# esp32.net
KiCad netlist of a schematic drawn in EAGLE
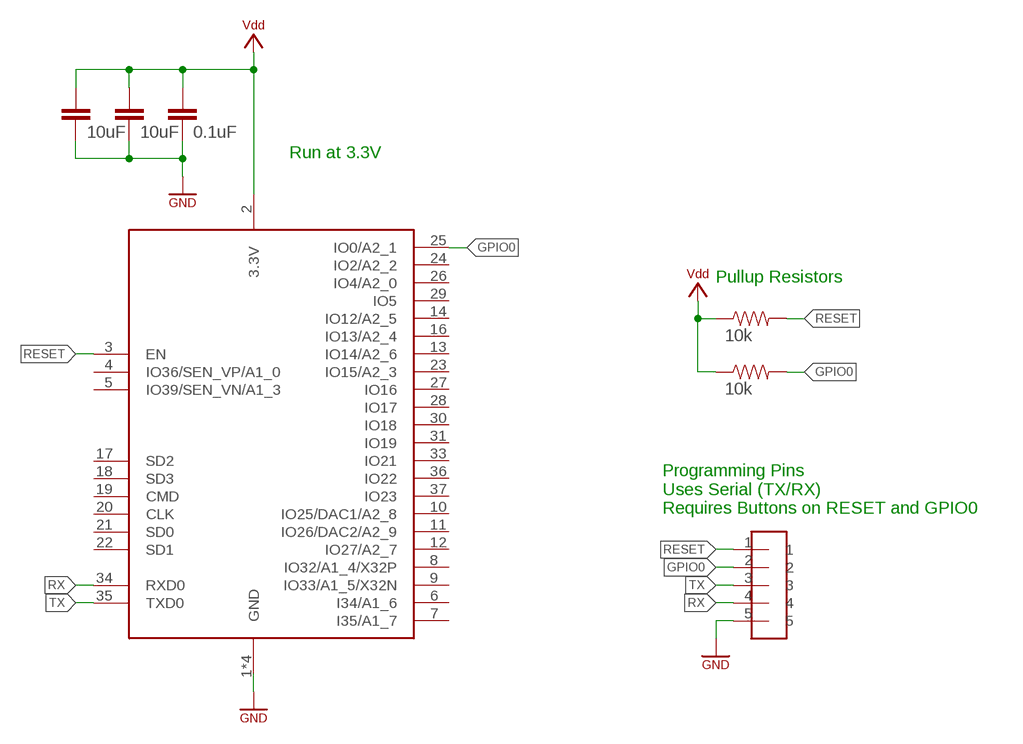
[diagram p0: schematic, sheet 1]

(export (version "E")
  (design (tool "Eeschema 10.0.6"))
  (components
    (comp (ref "C1")
      (value "0.1uF")
      (footprint "eagle-import:0805")
      (libsource (lib "eagle-import") (part "COMPONENT_CAP-0805"))
    )
    (comp (ref "C2")
      (value "10uF")
      (footprint "eagle-import:0805")
      (libsource (lib "eagle-import") (part "COMPONENT_CAP-0805"))
    )
    (comp (ref "C3")
      (value "10uF")
      (footprint "eagle-import:0805")
      (libsource (lib "eagle-import") (part "COMPONENT_CAP-0805"))
    )
    (comp (ref "R1")
      (value "10k")
      (footprint "eagle-import:0805")
      (libsource (lib "eagle-import") (part "COMPONENT_RESISTOR-0805"))
    )
    (comp (ref "R2")
      (value "10k")
      (footprint "eagle-import:0805")
      (libsource (lib "eagle-import") (part "COMPONENT_RESISTOR-0805"))
    )
    (comp (ref "U$1")
      (value "HEADER-5-TESTPOINT")
      (footprint "eagle-import:TESTPOINT-5")
      (libsource (lib "eagle-import") (part "HEADER-5-TESTPOINT"))
    )
    (comp (ref "X1")
      (value "MICRO_ESP32")
      (footprint "eagle-import:WROOM32")
      (libsource (lib "eagle-import") (part "MICRO_ESP32"))
    )
  )
  (nets
    (net (code "1") (name "GPIO0") (class "Default")
      (node (ref "R2") (pin "2") (pinfunction "2_2") (pintype "passive"))
      (node (ref "U$1") (pin "2") (pinfunction "2_2") (pintype "bidirectional"))
      (node (ref "X1") (pin "25") (pinfunction "IO0/A2_1_25") (pintype "bidirectional"))
    )
    (net (code "2") (name "RESET") (class "Default")
      (node (ref "R1") (pin "2") (pinfunction "2_2") (pintype "passive"))
      (node (ref "U$1") (pin "1") (pinfunction "1_1") (pintype "bidirectional"))
      (node (ref "X1") (pin "3") (pinfunction "EN_3") (pintype "input"))
    )
    (net (code "3") (name "RX") (class "Default")
      (node (ref "U$1") (pin "4") (pinfunction "4_4") (pintype "bidirectional"))
      (node (ref "X1") (pin "34") (pinfunction "RXD0_34") (pintype "input"))
    )
    (net (code "4") (name "SYMBOL_GND") (class "Default")
      (node (ref "C1") (pin "2") (pinfunction "2_2") (pintype "passive"))
      (node (ref "C2") (pin "2") (pinfunction "2_2") (pintype "passive"))
      (node (ref "C3") (pin "2") (pinfunction "2_2") (pintype "passive"))
      (node (ref "U$1") (pin "5") (pinfunction "5_5") (pintype "bidirectional"))
      (node (ref "X1") (pin "1") (pinfunction "GND_1") (pintype "passive"))
      (node (ref "X1") (pin "15") (pinfunction "GND_15") (pintype "passive"))
      (node (ref "X1") (pin "38") (pinfunction "GND_38") (pintype "passive"))
      (node (ref "X1") (pin "P$1") (pinfunction "GND_P$1") (pintype "passive"))
    )
    (net (code "5") (name "SYMBOL_VDD") (class "Default")
      (node (ref "C1") (pin "1") (pinfunction "1_1") (pintype "passive"))
      (node (ref "C2") (pin "1") (pinfunction "1_1") (pintype "passive"))
      (node (ref "C3") (pin "1") (pinfunction "1_1") (pintype "passive"))
      (node (ref "R1") (pin "1") (pinfunction "1_1") (pintype "passive"))
      (node (ref "R2") (pin "1") (pinfunction "1_1") (pintype "passive"))
      (node (ref "X1") (pin "2") (pinfunction "3.3V_2") (pintype "passive"))
    )
    (net (code "6") (name "TX") (class "Default")
      (node (ref "U$1") (pin "3") (pinfunction "3_3") (pintype "bidirectional"))
      (node (ref "X1") (pin "35") (pinfunction "TXD0_35") (pintype "output"))
    )
    (net (code "7") (name "unconnected-(X1-CLK-Pad20)") (class "Default")
      (node (ref "X1") (pin "20") (pinfunction "CLK_20") (pintype "bidirectional"))
    )
    (net (code "8") (name "unconnected-(X1-CMD-Pad19)") (class "Default")
      (node (ref "X1") (pin "19") (pinfunction "CMD_19") (pintype "bidirectional"))
    )
    (net (code "9") (name "unconnected-(X1-I34{slash}A1_6-Pad6)") (class "Default")
      (node (ref "X1") (pin "6") (pinfunction "I34/A1_6_6") (pintype "bidirectional"))
    )
    (net (code "10") (name "unconnected-(X1-I35{slash}A1_7-Pad7)") (class "Default")
      (node (ref "X1") (pin "7") (pinfunction "I35/A1_7_7") (pintype "bidirectional"))
    )
    (net (code "11") (name "unconnected-(X1-IO2{slash}A2_2-Pad24)") (class "Default")
      (node (ref "X1") (pin "24") (pinfunction "IO2/A2_2_24") (pintype "bidirectional"))
    )
    (net (code "12") (name "unconnected-(X1-IO4{slash}A2_0-Pad26)") (class "Default")
      (node (ref "X1") (pin "26") (pinfunction "IO4/A2_0_26") (pintype "bidirectional"))
    )
    (net (code "13") (name "unconnected-(X1-IO5-Pad29)") (class "Default")
      (node (ref "X1") (pin "29") (pinfunction "IO5_29") (pintype "bidirectional"))
    )
    (net (code "14") (name "unconnected-(X1-IO12{slash}A2_5-Pad14)") (class "Default")
      (node (ref "X1") (pin "14") (pinfunction "IO12/A2_5_14") (pintype "bidirectional"))
    )
    (net (code "15") (name "unconnected-(X1-IO13{slash}A2_4-Pad16)") (class "Default")
      (node (ref "X1") (pin "16") (pinfunction "IO13/A2_4_16") (pintype "bidirectional"))
    )
    (net (code "16") (name "unconnected-(X1-IO14{slash}A2_6-Pad13)") (class "Default")
      (node (ref "X1") (pin "13") (pinfunction "IO14/A2_6_13") (pintype "bidirectional"))
    )
    (net (code "17") (name "unconnected-(X1-IO15{slash}A2_3-Pad23)") (class "Default")
      (node (ref "X1") (pin "23") (pinfunction "IO15/A2_3_23") (pintype "bidirectional"))
    )
    (net (code "18") (name "unconnected-(X1-IO16-Pad27)") (class "Default")
      (node (ref "X1") (pin "27") (pinfunction "IO16_27") (pintype "bidirectional"))
    )
    (net (code "19") (name "unconnected-(X1-IO17-Pad28)") (class "Default")
      (node (ref "X1") (pin "28") (pinfunction "IO17_28") (pintype "bidirectional"))
    )
    (net (code "20") (name "unconnected-(X1-IO18-Pad30)") (class "Default")
      (node (ref "X1") (pin "30") (pinfunction "IO18_30") (pintype "bidirectional"))
    )
    (net (code "21") (name "unconnected-(X1-IO19-Pad31)") (class "Default")
      (node (ref "X1") (pin "31") (pinfunction "IO19_31") (pintype "bidirectional"))
    )
    (net (code "22") (name "unconnected-(X1-IO21-Pad33)") (class "Default")
      (node (ref "X1") (pin "33") (pinfunction "IO21_33") (pintype "bidirectional"))
    )
    (net (code "23") (name "unconnected-(X1-IO22-Pad36)") (class "Default")
      (node (ref "X1") (pin "36") (pinfunction "IO22_36") (pintype "bidirectional"))
    )
    (net (code "24") (name "unconnected-(X1-IO23-Pad37)") (class "Default")
      (node (ref "X1") (pin "37") (pinfunction "IO23_37") (pintype "bidirectional"))
    )
    (net (code "25") (name "unconnected-(X1-IO25{slash}DAC1{slash}A2_8-Pad10)") (class "Default")
      (node (ref "X1") (pin "10") (pinfunction "IO25/DAC1/A2_8_10") (pintype "bidirectional"))
    )
    (net (code "26") (name "unconnected-(X1-IO26{slash}DAC2{slash}A2_9-Pad11)") (class "Default")
      (node (ref "X1") (pin "11") (pinfunction "IO26/DAC2/A2_9_11") (pintype "bidirectional"))
    )
    (net (code "27") (name "unconnected-(X1-IO27{slash}A2_7-Pad12)") (class "Default")
      (node (ref "X1") (pin "12") (pinfunction "IO27/A2_7_12") (pintype "bidirectional"))
    )
    (net (code "28") (name "unconnected-(X1-IO32{slash}A1_4{slash}X32P-Pad8)") (class "Default")
      (node (ref "X1") (pin "8") (pinfunction "IO32/A1_4/X32P_8") (pintype "bidirectional"))
    )
    (net (code "29") (name "unconnected-(X1-IO33{slash}A1_5{slash}X32N-Pad9)") (class "Default")
      (node (ref "X1") (pin "9") (pinfunction "IO33/A1_5/X32N_9") (pintype "bidirectional"))
    )
    (net (code "30") (name "unconnected-(X1-IO36{slash}SEN_VP{slash}A1_0-Pad4)") (class "Default")
      (node (ref "X1") (pin "4") (pinfunction "IO36/SEN_VP/A1_0_4") (pintype "passive"))
    )
    (net (code "31") (name "unconnected-(X1-IO39{slash}SEN_VN{slash}A1_3-Pad5)") (class "Default")
      (node (ref "X1") (pin "5") (pinfunction "IO39/SEN_VN/A1_3_5") (pintype "passive"))
    )
    (net (code "32") (name "unconnected-(X1-SD0-Pad21)") (class "Default")
      (node (ref "X1") (pin "21") (pinfunction "SD0_21") (pintype "bidirectional"))
    )
    (net (code "33") (name "unconnected-(X1-SD1-Pad22)") (class "Default")
      (node (ref "X1") (pin "22") (pinfunction "SD1_22") (pintype "bidirectional"))
    )
    (net (code "34") (name "unconnected-(X1-SD2-Pad17)") (class "Default")
      (node (ref "X1") (pin "17") (pinfunction "SD2_17") (pintype "bidirectional"))
    )
    (net (code "35") (name "unconnected-(X1-SD3-Pad18)") (class "Default")
      (node (ref "X1") (pin "18") (pinfunction "SD3_18") (pintype "bidirectional"))
    )
  )
)
